# Orbiter_V1.net
KiCad netlist of a schematic drawn in EAGLE
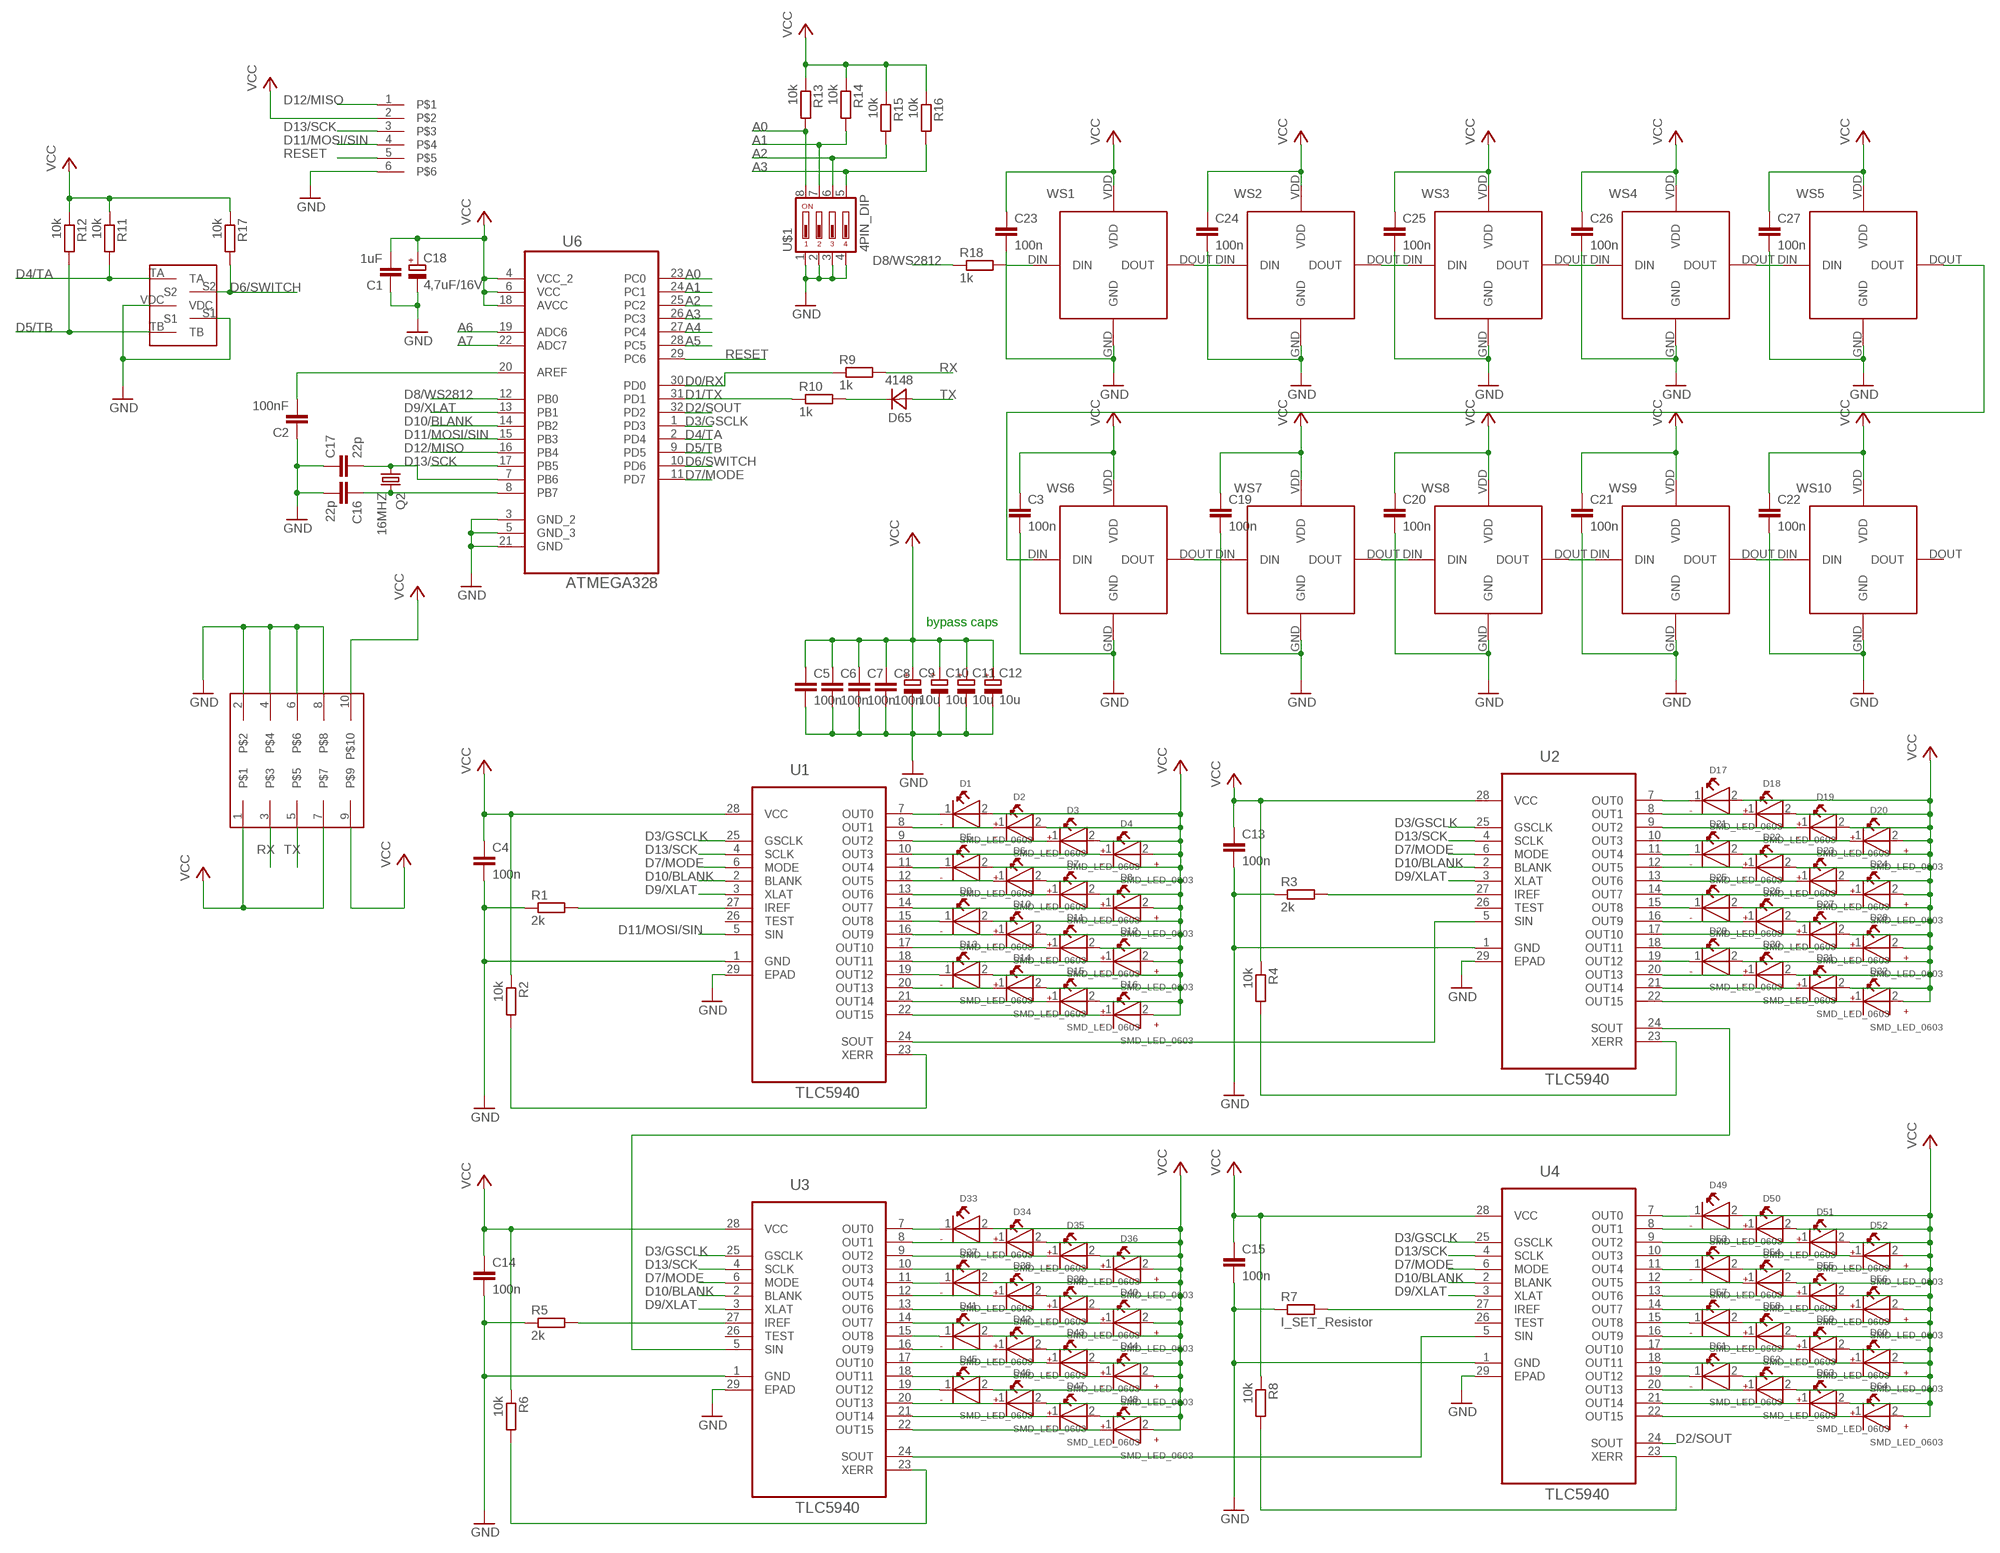
[diagram p0: schematic, sheet 1]

(export (version "E")
  (design (tool "Eeschema 10.0.6"))
  (components
    (comp (ref "C1")
      (value "1uF")
      (footprint "eagle-import:C0603")
      (libsource (lib "eagle-import") (part "KONDENSATOR_0603"))
    )
    (comp (ref "C2")
      (value "100nF")
      (footprint "eagle-import:C0603")
      (libsource (lib "eagle-import") (part "KONDENSATOR_0603"))
    )
    (comp (ref "C3")
      (value "100n")
      (footprint "eagle-import:C0603")
      (libsource (lib "eagle-import") (part "KONDENSATOR_0603"))
    )
    (comp (ref "C4")
      (value "100n")
      (footprint "eagle-import:C0603")
      (libsource (lib "eagle-import") (part "KONDENSATOR_0603"))
    )
    (comp (ref "C5")
      (value "100n")
      (footprint "eagle-import:C0603")
      (libsource (lib "eagle-import") (part "KONDENSATOR_0603"))
    )
    (comp (ref "C6")
      (value "100n")
      (footprint "eagle-import:C0603")
      (libsource (lib "eagle-import") (part "KONDENSATOR_0603"))
    )
    (comp (ref "C7")
      (value "100n")
      (footprint "eagle-import:C0603")
      (libsource (lib "eagle-import") (part "KONDENSATOR_0603"))
    )
    (comp (ref "C8")
      (value "100n")
      (footprint "eagle-import:C0603")
      (libsource (lib "eagle-import") (part "KONDENSATOR_0603"))
    )
    (comp (ref "C9")
      (value "10u")
      (footprint "eagle-import:153CLV-0605")
      (libsource (lib "eagle-import") (part "SMD_ELCTROLYTIC"))
    )
    (comp (ref "C10")
      (value "10u")
      (footprint "eagle-import:153CLV-0605")
      (libsource (lib "eagle-import") (part "SMD_ELCTROLYTIC"))
    )
    (comp (ref "C11")
      (value "10u")
      (footprint "eagle-import:153CLV-0605")
      (libsource (lib "eagle-import") (part "SMD_ELCTROLYTIC"))
    )
    (comp (ref "C12")
      (value "10u")
      (footprint "eagle-import:153CLV-0605")
      (libsource (lib "eagle-import") (part "SMD_ELCTROLYTIC"))
    )
    (comp (ref "C13")
      (value "100n")
      (footprint "eagle-import:C0603")
      (libsource (lib "eagle-import") (part "KONDENSATOR_0603"))
    )
    (comp (ref "C14")
      (value "100n")
      (footprint "eagle-import:C0603")
      (libsource (lib "eagle-import") (part "KONDENSATOR_0603"))
    )
    (comp (ref "C15")
      (value "100n")
      (footprint "eagle-import:C0603")
      (libsource (lib "eagle-import") (part "KONDENSATOR_0603"))
    )
    (comp (ref "C16")
      (value "22p")
      (footprint "eagle-import:C0603")
      (libsource (lib "eagle-import") (part "KONDENSATOR_0603"))
    )
    (comp (ref "C17")
      (value "22p")
      (footprint "eagle-import:C0603")
      (libsource (lib "eagle-import") (part "KONDENSATOR_0603"))
    )
    (comp (ref "C18")
      (value "4,7uF/16V")
      (footprint "eagle-import:153CLV-0605")
      (libsource (lib "eagle-import") (part "SMD_ELCTROLYTIC"))
    )
    (comp (ref "C19")
      (value "100n")
      (footprint "eagle-import:C0603")
      (libsource (lib "eagle-import") (part "KONDENSATOR_0603"))
    )
    (comp (ref "C20")
      (value "100n")
      (footprint "eagle-import:C0603")
      (libsource (lib "eagle-import") (part "KONDENSATOR_0603"))
    )
    (comp (ref "C21")
      (value "100n")
      (footprint "eagle-import:C0603")
      (libsource (lib "eagle-import") (part "KONDENSATOR_0603"))
    )
    (comp (ref "C22")
      (value "100n")
      (footprint "eagle-import:C0603")
      (libsource (lib "eagle-import") (part "KONDENSATOR_0603"))
    )
    (comp (ref "C23")
      (value "100n")
      (footprint "eagle-import:C0603")
      (libsource (lib "eagle-import") (part "KONDENSATOR_0603"))
    )
    (comp (ref "C24")
      (value "100n")
      (footprint "eagle-import:C0603")
      (libsource (lib "eagle-import") (part "KONDENSATOR_0603"))
    )
    (comp (ref "C25")
      (value "100n")
      (footprint "eagle-import:C0603")
      (libsource (lib "eagle-import") (part "KONDENSATOR_0603"))
    )
    (comp (ref "C26")
      (value "100n")
      (footprint "eagle-import:C0603")
      (libsource (lib "eagle-import") (part "KONDENSATOR_0603"))
    )
    (comp (ref "C27")
      (value "100n")
      (footprint "eagle-import:C0603")
      (libsource (lib "eagle-import") (part "KONDENSATOR_0603"))
    )
    (comp (ref "D1")
      (value "SMD_LED_0603")
      (footprint "eagle-import:WL-SMCW_0603")
      (libsource (lib "eagle-import") (part "SMD_LED_0603"))
    )
    (comp (ref "D2")
      (value "SMD_LED_0603")
      (footprint "eagle-import:WL-SMCW_0603")
      (libsource (lib "eagle-import") (part "SMD_LED_0603"))
    )
    (comp (ref "D3")
      (value "SMD_LED_0603")
      (footprint "eagle-import:WL-SMCW_0603")
      (libsource (lib "eagle-import") (part "SMD_LED_0603"))
    )
    (comp (ref "D4")
      (value "SMD_LED_0603")
      (footprint "eagle-import:WL-SMCW_0603")
      (libsource (lib "eagle-import") (part "SMD_LED_0603"))
    )
    (comp (ref "D5")
      (value "SMD_LED_0603")
      (footprint "eagle-import:WL-SMCW_0603")
      (libsource (lib "eagle-import") (part "SMD_LED_0603"))
    )
    (comp (ref "D6")
      (value "SMD_LED_0603")
      (footprint "eagle-import:WL-SMCW_0603")
      (libsource (lib "eagle-import") (part "SMD_LED_0603"))
    )
    (comp (ref "D7")
      (value "SMD_LED_0603")
      (footprint "eagle-import:WL-SMCW_0603")
      (libsource (lib "eagle-import") (part "SMD_LED_0603"))
    )
    (comp (ref "D8")
      (value "SMD_LED_0603")
      (footprint "eagle-import:WL-SMCW_0603")
      (libsource (lib "eagle-import") (part "SMD_LED_0603"))
    )
    (comp (ref "D9")
      (value "SMD_LED_0603")
      (footprint "eagle-import:WL-SMCW_0603")
      (libsource (lib "eagle-import") (part "SMD_LED_0603"))
    )
    (comp (ref "D10")
      (value "SMD_LED_0603")
      (footprint "eagle-import:WL-SMCW_0603")
      (libsource (lib "eagle-import") (part "SMD_LED_0603"))
    )
    (comp (ref "D11")
      (value "SMD_LED_0603")
      (footprint "eagle-import:WL-SMCW_0603")
      (libsource (lib "eagle-import") (part "SMD_LED_0603"))
    )
    (comp (ref "D12")
      (value "SMD_LED_0603")
      (footprint "eagle-import:WL-SMCW_0603")
      (libsource (lib "eagle-import") (part "SMD_LED_0603"))
    )
    (comp (ref "D13")
      (value "SMD_LED_0603")
      (footprint "eagle-import:WL-SMCW_0603")
      (libsource (lib "eagle-import") (part "SMD_LED_0603"))
    )
    (comp (ref "D14")
      (value "SMD_LED_0603")
      (footprint "eagle-import:WL-SMCW_0603")
      (libsource (lib "eagle-import") (part "SMD_LED_0603"))
    )
    (comp (ref "D15")
      (value "SMD_LED_0603")
      (footprint "eagle-import:WL-SMCW_0603")
      (libsource (lib "eagle-import") (part "SMD_LED_0603"))
    )
    (comp (ref "D16")
      (value "SMD_LED_0603")
      (footprint "eagle-import:WL-SMCW_0603")
      (libsource (lib "eagle-import") (part "SMD_LED_0603"))
    )
    (comp (ref "D17")
      (value "SMD_LED_0603")
      (footprint "eagle-import:WL-SMCW_0603")
      (libsource (lib "eagle-import") (part "SMD_LED_0603"))
    )
    (comp (ref "D18")
      (value "SMD_LED_0603")
      (footprint "eagle-import:WL-SMCW_0603")
      (libsource (lib "eagle-import") (part "SMD_LED_0603"))
    )
    (comp (ref "D19")
      (value "SMD_LED_0603")
      (footprint "eagle-import:WL-SMCW_0603")
      (libsource (lib "eagle-import") (part "SMD_LED_0603"))
    )
    (comp (ref "D20")
      (value "SMD_LED_0603")
      (footprint "eagle-import:WL-SMCW_0603")
      (libsource (lib "eagle-import") (part "SMD_LED_0603"))
    )
    (comp (ref "D21")
      (value "SMD_LED_0603")
      (footprint "eagle-import:WL-SMCW_0603")
      (libsource (lib "eagle-import") (part "SMD_LED_0603"))
    )
    (comp (ref "D22")
      (value "SMD_LED_0603")
      (footprint "eagle-import:WL-SMCW_0603")
      (libsource (lib "eagle-import") (part "SMD_LED_0603"))
    )
    (comp (ref "D23")
      (value "SMD_LED_0603")
      (footprint "eagle-import:WL-SMCW_0603")
      (libsource (lib "eagle-import") (part "SMD_LED_0603"))
    )
    (comp (ref "D24")
      (value "SMD_LED_0603")
      (footprint "eagle-import:WL-SMCW_0603")
      (libsource (lib "eagle-import") (part "SMD_LED_0603"))
    )
    (comp (ref "D25")
      (value "SMD_LED_0603")
      (footprint "eagle-import:WL-SMCW_0603")
      (libsource (lib "eagle-import") (part "SMD_LED_0603"))
    )
    (comp (ref "D26")
      (value "SMD_LED_0603")
      (footprint "eagle-import:WL-SMCW_0603")
      (libsource (lib "eagle-import") (part "SMD_LED_0603"))
    )
    (comp (ref "D27")
      (value "SMD_LED_0603")
      (footprint "eagle-import:WL-SMCW_0603")
      (libsource (lib "eagle-import") (part "SMD_LED_0603"))
    )
    (comp (ref "D28")
      (value "SMD_LED_0603")
      (footprint "eagle-import:WL-SMCW_0603")
      (libsource (lib "eagle-import") (part "SMD_LED_0603"))
    )
    (comp (ref "D29")
      (value "SMD_LED_0603")
      (footprint "eagle-import:WL-SMCW_0603")
      (libsource (lib "eagle-import") (part "SMD_LED_0603"))
    )
    (comp (ref "D30")
      (value "SMD_LED_0603")
      (footprint "eagle-import:WL-SMCW_0603")
      (libsource (lib "eagle-import") (part "SMD_LED_0603"))
    )
    (comp (ref "D31")
      (value "SMD_LED_0603")
      (footprint "eagle-import:WL-SMCW_0603")
      (libsource (lib "eagle-import") (part "SMD_LED_0603"))
    )
    (comp (ref "D32")
      (value "SMD_LED_0603")
      (footprint "eagle-import:WL-SMCW_0603")
      (libsource (lib "eagle-import") (part "SMD_LED_0603"))
    )
    (comp (ref "D33")
      (value "SMD_LED_0603")
      (footprint "eagle-import:WL-SMCW_0603")
      (libsource (lib "eagle-import") (part "SMD_LED_0603"))
    )
    (comp (ref "D34")
      (value "SMD_LED_0603")
      (footprint "eagle-import:WL-SMCW_0603")
      (libsource (lib "eagle-import") (part "SMD_LED_0603"))
    )
    (comp (ref "D35")
      (value "SMD_LED_0603")
      (footprint "eagle-import:WL-SMCW_0603")
      (libsource (lib "eagle-import") (part "SMD_LED_0603"))
    )
    (comp (ref "D36")
      (value "SMD_LED_0603")
      (footprint "eagle-import:WL-SMCW_0603")
      (libsource (lib "eagle-import") (part "SMD_LED_0603"))
    )
    (comp (ref "D37")
      (value "SMD_LED_0603")
      (footprint "eagle-import:WL-SMCW_0603")
      (libsource (lib "eagle-import") (part "SMD_LED_0603"))
    )
    (comp (ref "D38")
      (value "SMD_LED_0603")
      (footprint "eagle-import:WL-SMCW_0603")
      (libsource (lib "eagle-import") (part "SMD_LED_0603"))
    )
    (comp (ref "D39")
      (value "SMD_LED_0603")
      (footprint "eagle-import:WL-SMCW_0603")
      (libsource (lib "eagle-import") (part "SMD_LED_0603"))
    )
    (comp (ref "D40")
      (value "SMD_LED_0603")
      (footprint "eagle-import:WL-SMCW_0603")
      (libsource (lib "eagle-import") (part "SMD_LED_0603"))
    )
    (comp (ref "D41")
      (value "SMD_LED_0603")
      (footprint "eagle-import:WL-SMCW_0603")
      (libsource (lib "eagle-import") (part "SMD_LED_0603"))
    )
    (comp (ref "D42")
      (value "SMD_LED_0603")
      (footprint "eagle-import:WL-SMCW_0603")
      (libsource (lib "eagle-import") (part "SMD_LED_0603"))
    )
    (comp (ref "D43")
      (value "SMD_LED_0603")
      (footprint "eagle-import:WL-SMCW_0603")
      (libsource (lib "eagle-import") (part "SMD_LED_0603"))
    )
    (comp (ref "D44")
      (value "SMD_LED_0603")
      (footprint "eagle-import:WL-SMCW_0603")
      (libsource (lib "eagle-import") (part "SMD_LED_0603"))
    )
    (comp (ref "D45")
      (value "SMD_LED_0603")
      (footprint "eagle-import:WL-SMCW_0603")
      (libsource (lib "eagle-import") (part "SMD_LED_0603"))
    )
    (comp (ref "D46")
      (value "SMD_LED_0603")
      (footprint "eagle-import:WL-SMCW_0603")
      (libsource (lib "eagle-import") (part "SMD_LED_0603"))
    )
    (comp (ref "D47")
      (value "SMD_LED_0603")
      (footprint "eagle-import:WL-SMCW_0603")
      (libsource (lib "eagle-import") (part "SMD_LED_0603"))
    )
    (comp (ref "D48")
      (value "SMD_LED_0603")
      (footprint "eagle-import:WL-SMCW_0603")
      (libsource (lib "eagle-import") (part "SMD_LED_0603"))
    )
    (comp (ref "D49")
      (value "SMD_LED_0603")
      (footprint "eagle-import:WL-SMCW_0603")
      (libsource (lib "eagle-import") (part "SMD_LED_0603"))
    )
    (comp (ref "D50")
      (value "SMD_LED_0603")
      (footprint "eagle-import:WL-SMCW_0603")
      (libsource (lib "eagle-import") (part "SMD_LED_0603"))
    )
    (comp (ref "D51")
      (value "SMD_LED_0603")
      (footprint "eagle-import:WL-SMCW_0603")
      (libsource (lib "eagle-import") (part "SMD_LED_0603"))
    )
    (comp (ref "D52")
      (value "SMD_LED_0603")
      (footprint "eagle-import:WL-SMCW_0603")
      (libsource (lib "eagle-import") (part "SMD_LED_0603"))
    )
    (comp (ref "D53")
      (value "SMD_LED_0603")
      (footprint "eagle-import:WL-SMCW_0603")
      (libsource (lib "eagle-import") (part "SMD_LED_0603"))
    )
    (comp (ref "D54")
      (value "SMD_LED_0603")
      (footprint "eagle-import:WL-SMCW_0603")
      (libsource (lib "eagle-import") (part "SMD_LED_0603"))
    )
    (comp (ref "D55")
      (value "SMD_LED_0603")
      (footprint "eagle-import:WL-SMCW_0603")
      (libsource (lib "eagle-import") (part "SMD_LED_0603"))
    )
    (comp (ref "D56")
      (value "SMD_LED_0603")
      (footprint "eagle-import:WL-SMCW_0603")
      (libsource (lib "eagle-import") (part "SMD_LED_0603"))
    )
    (comp (ref "D57")
      (value "SMD_LED_0603")
      (footprint "eagle-import:WL-SMCW_0603")
      (libsource (lib "eagle-import") (part "SMD_LED_0603"))
    )
    (comp (ref "D58")
      (value "SMD_LED_0603")
      (footprint "eagle-import:WL-SMCW_0603")
      (libsource (lib "eagle-import") (part "SMD_LED_0603"))
    )
    (comp (ref "D59")
      (value "SMD_LED_0603")
      (footprint "eagle-import:WL-SMCW_0603")
      (libsource (lib "eagle-import") (part "SMD_LED_0603"))
    )
    (comp (ref "D60")
      (value "SMD_LED_0603")
      (footprint "eagle-import:WL-SMCW_0603")
      (libsource (lib "eagle-import") (part "SMD_LED_0603"))
    )
    (comp (ref "D61")
      (value "SMD_LED_0603")
      (footprint "eagle-import:WL-SMCW_0603")
      (libsource (lib "eagle-import") (part "SMD_LED_0603"))
    )
    (comp (ref "D62")
      (value "SMD_LED_0603")
      (footprint "eagle-import:WL-SMCW_0603")
      (libsource (lib "eagle-import") (part "SMD_LED_0603"))
    )
    (comp (ref "D63")
      (value "SMD_LED_0603")
      (footprint "eagle-import:WL-SMCW_0603")
      (libsource (lib "eagle-import") (part "SMD_LED_0603"))
    )
    (comp (ref "D64")
      (value "SMD_LED_0603")
      (footprint "eagle-import:WL-SMCW_0603")
      (libsource (lib "eagle-import") (part "SMD_LED_0603"))
    )
    (comp (ref "D65")
      (value "4148")
      (footprint "eagle-import:SOD323-R")
      (libsource (lib "eagle-import") (part "4148_SOD323"))
    )
    (comp (ref "Q2")
      (value "16MHZ")
      (footprint "eagle-import:SM49")
      (libsource (lib "eagle-import") (part "CRYSTAL_SM49"))
    )
    (comp (ref "R1")
      (value "2k")
      (footprint "eagle-import:R0805")
      (libsource (lib "eagle-import") (part "WIDERSTAND_0805R0805"))
    )
    (comp (ref "R2")
      (value "10k")
      (footprint "eagle-import:R0805")
      (libsource (lib "eagle-import") (part "WIDERSTAND_0805R0805"))
    )
    (comp (ref "R3")
      (value "2k")
      (footprint "eagle-import:R0805")
      (libsource (lib "eagle-import") (part "WIDERSTAND_0805R0805"))
    )
    (comp (ref "R4")
      (value "10k")
      (footprint "eagle-import:R0805")
      (libsource (lib "eagle-import") (part "WIDERSTAND_0805R0805"))
    )
    (comp (ref "R5")
      (value "2k")
      (footprint "eagle-import:R0805")
      (libsource (lib "eagle-import") (part "WIDERSTAND_0805R0805"))
    )
    (comp (ref "R6")
      (value "10k")
      (footprint "eagle-import:R0805")
      (libsource (lib "eagle-import") (part "WIDERSTAND_0805R0805"))
    )
    (comp (ref "R7")
      (value "I_SET_Resistor")
      (footprint "eagle-import:R0805")
      (libsource (lib "eagle-import") (part "WIDERSTAND_0805R0805"))
    )
    (comp (ref "R8")
      (value "10k")
      (footprint "eagle-import:R0805")
      (libsource (lib "eagle-import") (part "WIDERSTAND_0805R0805"))
    )
    (comp (ref "R9")
      (value "1k")
      (footprint "eagle-import:R0805")
      (libsource (lib "eagle-import") (part "WIDERSTAND_0805R0805"))
    )
    (comp (ref "R10")
      (value "1k")
      (footprint "eagle-import:R0805")
      (libsource (lib "eagle-import") (part "WIDERSTAND_0805R0805"))
    )
    (comp (ref "R11")
      (value "10k")
      (footprint "eagle-import:R0805")
      (libsource (lib "eagle-import") (part "WIDERSTAND_0805R0805"))
    )
    (comp (ref "R12")
      (value "10k")
      (footprint "eagle-import:R0805")
      (libsource (lib "eagle-import") (part "WIDERSTAND_0805R0805"))
    )
    (comp (ref "R13")
      (value "10k")
      (footprint "eagle-import:R0805")
      (libsource (lib "eagle-import") (part "WIDERSTAND_0805R0805"))
    )
    (comp (ref "R14")
      (value "10k")
      (footprint "eagle-import:R0805")
      (libsource (lib "eagle-import") (part "WIDERSTAND_0805R0805"))
    )
    (comp (ref "R15")
      (value "10k")
      (footprint "eagle-import:R0805")
      (libsource (lib "eagle-import") (part "WIDERSTAND_0805R0805"))
    )
    (comp (ref "R16")
      (value "10k")
      (footprint "eagle-import:R0805")
      (libsource (lib "eagle-import") (part "WIDERSTAND_0805R0805"))
    )
    (comp (ref "R17")
      (value "10k")
      (footprint "eagle-import:R0805")
      (libsource (lib "eagle-import") (part "WIDERSTAND_0805R0805"))
    )
    (comp (ref "R18")
      (value "1k")
      (footprint "eagle-import:R0805")
      (libsource (lib "eagle-import") (part "WIDERSTAND_0805R0805"))
    )
    (comp (ref "U$1")
      (value "4PIN_DIP")
      (footprint "eagle-import:CTS-219-04")
      (libsource (lib "eagle-import") (part "4PIN_DIP"))
    )
    (comp (ref "U$2")
      (value "10PIN_HEADER_SMD")
      (footprint "eagle-import:87832-10")
      (libsource (lib "eagle-import") (part "10PIN_HEADER_SMD"))
    )
    (comp (ref "U$3")
      (value "6PIN_HEADER_SMD_OPEN")
      (footprint "eagle-import:6PIN_HEADER_SMD_OPEN")
      (libsource (lib "eagle-import") (part "6PIN_HEADER_SMD_OPEN"))
    )
    (comp (ref "U$4")
      (value "BOURNS_ENCODER")
      (footprint "eagle-import:BOURNS_ENCODER_SMD")
      (libsource (lib "eagle-import") (part "BOURNS_ENCODER"))
    )
    (comp (ref "U1")
      (value "TLC5940")
      (footprint "eagle-import:SOP65P640X120-29N")
      (fields (field (name "MPN") "TLC59401PWP"))
      (libsource (lib "eagle-import") (part "TLC59401PWP"))
    )
    (comp (ref "U2")
      (value "TLC5940")
      (footprint "eagle-import:SOP65P640X120-29N")
      (fields (field (name "MPN") "TLC59401PWP"))
      (libsource (lib "eagle-import") (part "TLC59401PWP"))
    )
    (comp (ref "U3")
      (value "TLC5940")
      (footprint "eagle-import:SOP65P640X120-29N")
      (fields (field (name "MPN") "TLC59401PWP"))
      (libsource (lib "eagle-import") (part "TLC59401PWP"))
    )
    (comp (ref "U4")
      (value "TLC5940")
      (footprint "eagle-import:SOP65P640X120-29N")
      (fields (field (name "MPN") "TLC59401PWP"))
      (libsource (lib "eagle-import") (part "TLC59401PWP"))
    )
    (comp (ref "U6")
      (value "ATMEGA328")
      (footprint "eagle-import:QFP80P900X900X120-32N")
      (fields (field (name "MPN") "ATMEGA328P-AU"))
      (libsource (lib "eagle-import") (part "ATMEGA328P-AU"))
    )
    (comp (ref "WS1")
      (value "WS2812")
      (footprint "eagle-import:WS2812")
      (libsource (lib "eagle-import") (part "WS2812"))
    )
    (comp (ref "WS2")
      (value "WS2812")
      (footprint "eagle-import:WS2812")
      (libsource (lib "eagle-import") (part "WS2812"))
    )
    (comp (ref "WS3")
      (value "WS2812")
      (footprint "eagle-import:WS2812")
      (libsource (lib "eagle-import") (part "WS2812"))
    )
    (comp (ref "WS4")
      (value "WS2812")
      (footprint "eagle-import:WS2812")
      (libsource (lib "eagle-import") (part "WS2812"))
    )
    (comp (ref "WS5")
      (value "WS2812")
      (footprint "eagle-import:WS2812")
      (libsource (lib "eagle-import") (part "WS2812"))
    )
    (comp (ref "WS6")
      (value "WS2812")
      (footprint "eagle-import:WS2812")
      (libsource (lib "eagle-import") (part "WS2812"))
    )
    (comp (ref "WS7")
      (value "WS2812")
      (footprint "eagle-import:WS2812")
      (libsource (lib "eagle-import") (part "WS2812"))
    )
    (comp (ref "WS8")
      (value "WS2812")
      (footprint "eagle-import:WS2812")
      (libsource (lib "eagle-import") (part "WS2812"))
    )
    (comp (ref "WS9")
      (value "WS2812")
      (footprint "eagle-import:WS2812")
      (libsource (lib "eagle-import") (part "WS2812"))
    )
    (comp (ref "WS10")
      (value "WS2812")
      (footprint "eagle-import:WS2812")
      (libsource (lib "eagle-import") (part "WS2812"))
    )
  )
  (nets
    (net (code "1") (name "/A0") (class "Default")
      (node (ref "R13") (pin "2") (pinfunction "2_2") (pintype "passive"))
      (node (ref "U$1") (pin "8") (pinfunction "8_8") (pintype "passive"))
      (node (ref "U6") (pin "23") (pinfunction "PC0_23") (pintype "bidirectional"))
    )
    (net (code "2") (name "/A1") (class "Default")
      (node (ref "R14") (pin "2") (pinfunction "2_2") (pintype "passive"))
      (node (ref "U$1") (pin "7") (pinfunction "7_7") (pintype "passive"))
      (node (ref "U6") (pin "24") (pinfunction "PC1_24") (pintype "bidirectional"))
    )
    (net (code "3") (name "/A2") (class "Default")
      (node (ref "R15") (pin "2") (pinfunction "2_2") (pintype "passive"))
      (node (ref "U$1") (pin "6") (pinfunction "6_6") (pintype "passive"))
      (node (ref "U6") (pin "25") (pinfunction "PC2_25") (pintype "bidirectional"))
    )
    (net (code "4") (name "/A3") (class "Default")
      (node (ref "R16") (pin "2") (pinfunction "2_2") (pintype "passive"))
      (node (ref "U$1") (pin "5") (pinfunction "5_5") (pintype "passive"))
      (node (ref "U6") (pin "26") (pinfunction "PC3_26") (pintype "bidirectional"))
    )
    (net (code "5") (name "/A4") (class "Default")
      (node (ref "U6") (pin "27") (pinfunction "PC4_27") (pintype "bidirectional"))
    )
    (net (code "6") (name "/A5") (class "Default")
      (node (ref "U6") (pin "28") (pinfunction "PC5_28") (pintype "bidirectional"))
    )
    (net (code "7") (name "/A6") (class "Default")
      (node (ref "U6") (pin "19") (pinfunction "ADC6_19") (pintype "input"))
    )
    (net (code "8") (name "/A7") (class "Default")
      (node (ref "U6") (pin "22") (pinfunction "ADC7_22") (pintype "input"))
    )
    (net (code "9") (name "/D0{slash}RX") (class "Default")
      (node (ref "R9") (pin "1") (pinfunction "1_1") (pintype "passive"))
      (node (ref "U6") (pin "30") (pinfunction "PD0_30") (pintype "bidirectional"))
    )
    (net (code "10") (name "/D1{slash}TX") (class "Default")
      (node (ref "R10") (pin "1") (pinfunction "1_1") (pintype "passive"))
      (node (ref "U6") (pin "31") (pinfunction "PD1_31") (pintype "bidirectional"))
    )
    (net (code "11") (name "/D2{slash}SOUT") (class "Default")
      (node (ref "U4") (pin "24") (pinfunction "SOUT_24") (pintype "output"))
      (node (ref "U6") (pin "32") (pinfunction "PD2_32") (pintype "bidirectional"))
    )
    (net (code "12") (name "/D3{slash}GSCLK") (class "Default")
      (node (ref "U1") (pin "25") (pinfunction "GSCLK_25") (pintype "input"))
      (node (ref "U2") (pin "25") (pinfunction "GSCLK_25") (pintype "input"))
      (node (ref "U3") (pin "25") (pinfunction "GSCLK_25") (pintype "input"))
      (node (ref "U4") (pin "25") (pinfunction "GSCLK_25") (pintype "input"))
      (node (ref "U6") (pin "1") (pinfunction "PD3_1") (pintype "bidirectional"))
    )
    (net (code "13") (name "/D4{slash}TA") (class "Default")
      (node (ref "R11") (pin "2") (pinfunction "2_2") (pintype "passive"))
      (node (ref "U$4") (pin "TA") (pinfunction "TA_TA") (pintype "bidirectional"))
      (node (ref "U6") (pin "2") (pinfunction "PD4_2") (pintype "bidirectional"))
    )
    (net (code "14") (name "/D5{slash}TB") (class "Default")
      (node (ref "R12") (pin "2") (pinfunction "2_2") (pintype "passive"))
      (node (ref "U$4") (pin "TB") (pinfunction "TB_TB") (pintype "bidirectional"))
      (node (ref "U6") (pin "9") (pinfunction "PD5_9") (pintype "bidirectional"))
    )
    (net (code "15") (name "/D6{slash}SWITCH") (class "Default")
      (node (ref "R17") (pin "2") (pinfunction "2_2") (pintype "passive"))
      (node (ref "U$4") (pin "S2") (pinfunction "S2_S2") (pintype "bidirectional"))
      (node (ref "U6") (pin "10") (pinfunction "PD6_10") (pintype "bidirectional"))
    )
    (net (code "16") (name "/D7{slash}MODE") (class "Default")
      (node (ref "U1") (pin "6") (pinfunction "MODE_6") (pintype "input"))
      (node (ref "U2") (pin "6") (pinfunction "MODE_6") (pintype "input"))
      (node (ref "U3") (pin "6") (pinfunction "MODE_6") (pintype "input"))
      (node (ref "U4") (pin "6") (pinfunction "MODE_6") (pintype "input"))
      (node (ref "U6") (pin "11") (pinfunction "PD7_11") (pintype "bidirectional"))
    )
    (net (code "17") (name "/D8{slash}WS2812") (class "Default")
      (node (ref "R18") (pin "1") (pinfunction "1_1") (pintype "passive"))
      (node (ref "U6") (pin "12") (pinfunction "PB0_12") (pintype "bidirectional"))
    )
    (net (code "18") (name "/D9{slash}XLAT") (class "Default")
      (node (ref "U1") (pin "3") (pinfunction "XLAT_3") (pintype "input"))
      (node (ref "U2") (pin "3") (pinfunction "XLAT_3") (pintype "input"))
      (node (ref "U3") (pin "3") (pinfunction "XLAT_3") (pintype "input"))
      (node (ref "U4") (pin "3") (pinfunction "XLAT_3") (pintype "input"))
      (node (ref "U6") (pin "13") (pinfunction "PB1_13") (pintype "bidirectional"))
    )
    (net (code "19") (name "/D10{slash}BLANK") (class "Default")
      (node (ref "U1") (pin "2") (pinfunction "BLANK_2") (pintype "input"))
      (node (ref "U2") (pin "2") (pinfunction "BLANK_2") (pintype "input"))
      (node (ref "U3") (pin "2") (pinfunction "BLANK_2") (pintype "input"))
      (node (ref "U4") (pin "2") (pinfunction "BLANK_2") (pintype "input"))
      (node (ref "U6") (pin "14") (pinfunction "PB2_14") (pintype "bidirectional"))
    )
    (net (code "20") (name "/D11{slash}MOSI{slash}SIN") (class "Default")
      (node (ref "U$3") (pin "4") (pinfunction "P$4_4") (pintype "bidirectional"))
      (node (ref "U1") (pin "5") (pinfunction "SIN_5") (pintype "input"))
      (node (ref "U6") (pin "15") (pinfunction "PB3_15") (pintype "bidirectional"))
    )
    (net (code "21") (name "/D12{slash}MISO") (class "Default")
      (node (ref "U$3") (pin "1") (pinfunction "P$1_1") (pintype "bidirectional"))
      (node (ref "U6") (pin "16") (pinfunction "PB4_16") (pintype "bidirectional"))
    )
    (net (code "22") (name "/D13{slash}SCK") (class "Default")
      (node (ref "U$3") (pin "3") (pinfunction "P$3_3") (pintype "bidirectional"))
      (node (ref "U1") (pin "4") (pinfunction "SCLK_4") (pintype "input"))
      (node (ref "U2") (pin "4") (pinfunction "SCLK_4") (pintype "input"))
      (node (ref "U3") (pin "4") (pinfunction "SCLK_4") (pintype "input"))
      (node (ref "U4") (pin "4") (pinfunction "SCLK_4") (pintype "input"))
      (node (ref "U6") (pin "17") (pinfunction "PB5_17") (pintype "bidirectional"))
    )
    (net (code "23") (name "/RESET") (class "Default")
      (node (ref "U$3") (pin "5") (pinfunction "P$5_5") (pintype "bidirectional"))
      (node (ref "U6") (pin "29") (pinfunction "PC6_29") (pintype "bidirectional"))
    )
    (net (code "24") (name "/RX") (class "Default")
      (node (ref "R9") (pin "2") (pinfunction "2_2") (pintype "passive"))
      (node (ref "U$2") (pin "3") (pinfunction "P$3_3") (pintype "bidirectional"))
    )
    (net (code "25") (name "/TX") (class "Default")
      (node (ref "D65") (pin "A") (pinfunction "A_A") (pintype "passive"))
      (node (ref "U$2") (pin "5") (pinfunction "P$5_5") (pintype "bidirectional"))
    )
    (net (code "26") (name "GND") (class "Default")
      (node (ref "C1") (pin "1") (pinfunction "1_1") (pintype "passive"))
      (node (ref "C10") (pin "-") (pinfunction "-_-") (pintype "passive"))
      (node (ref "C11") (pin "-") (pinfunction "-_-") (pintype "passive"))
      (node (ref "C12") (pin "-") (pinfunction "-_-") (pintype "passive"))
      (node (ref "C13") (pin "2") (pinfunction "2_2") (pintype "passive"))
      (node (ref "C14") (pin "2") (pinfunction "2_2") (pintype "passive"))
      (node (ref "C15") (pin "2") (pinfunction "2_2") (pintype "passive"))
      (node (ref "C16") (pin "2") (pinfunction "2_2") (pintype "passive"))
      (node (ref "C17") (pin "1") (pinfunction "1_1") (pintype "passive"))
      (node (ref "C18") (pin "-") (pinfunction "-_-") (pintype "passive"))
      (node (ref "C19") (pin "2") (pinfunction "2_2") (pintype "passive"))
      (node (ref "C2") (pin "1") (pinfunction "1_1") (pintype "passive"))
      (node (ref "C20") (pin "2") (pinfunction "2_2") (pintype "passive"))
      (node (ref "C21") (pin "2") (pinfunction "2_2") (pintype "passive"))
      (node (ref "C22") (pin "2") (pinfunction "2_2") (pintype "passive"))
      (node (ref "C23") (pin "2") (pinfunction "2_2") (pintype "passive"))
      (node (ref "C24") (pin "2") (pinfunction "2_2") (pintype "passive"))
      (node (ref "C25") (pin "2") (pinfunction "2_2") (pintype "passive"))
      (node (ref "C26") (pin "2") (pinfunction "2_2") (pintype "passive"))
      (node (ref "C27") (pin "2") (pinfunction "2_2") (pintype "passive"))
      (node (ref "C3") (pin "2") (pinfunction "2_2") (pintype "passive"))
      (node (ref "C4") (pin "2") (pinfunction "2_2") (pintype "passive"))
      (node (ref "C5") (pin "2") (pinfunction "2_2") (pintype "passive"))
      (node (ref "C6") (pin "2") (pinfunction "2_2") (pintype "passive"))
      (node (ref "C7") (pin "2") (pinfunction "2_2") (pintype "passive"))
      (node (ref "C8") (pin "2") (pinfunction "2_2") (pintype "passive"))
      (node (ref "C9") (pin "-") (pinfunction "-_-") (pintype "passive"))
      (node (ref "R1") (pin "1") (pinfunction "1_1") (pintype "passive"))
      (node (ref "R3") (pin "1") (pinfunction "1_1") (pintype "passive"))
      (node (ref "R5") (pin "1") (pinfunction "1_1") (pintype "passive"))
      (node (ref "R7") (pin "1") (pinfunction "1_1") (pintype "passive"))
      (node (ref "U$1") (pin "1") (pinfunction "1_1") (pintype "passive"))
      (node (ref "U$1") (pin "2") (pinfunction "2_2") (pintype "passive"))
      (node (ref "U$1") (pin "3") (pinfunction "3_3") (pintype "passive"))
      (node (ref "U$1") (pin "4") (pinfunction "4_4") (pintype "passive"))
      (node (ref "U$2") (pin "2") (pinfunction "P$2_2") (pintype "bidirectional"))
      (node (ref "U$2") (pin "4") (pinfunction "P$4_4") (pintype "bidirectional"))
      (node (ref "U$2") (pin "6") (pinfunction "P$6_6") (pintype "bidirectional"))
      (node (ref "U$2") (pin "8") (pinfunction "P$8_8") (pintype "bidirectional"))
      (node (ref "U$3") (pin "6") (pinfunction "P$6_6") (pintype "bidirectional"))
      (node (ref "U$4") (pin "S1") (pinfunction "S1_S1") (pintype "bidirectional"))
      (node (ref "U$4") (pin "VDC") (pinfunction "VDC_VDC") (pintype "bidirectional"))
      (node (ref "U1") (pin "1") (pinfunction "GND_1") (pintype "passive"))
      (node (ref "U1") (pin "29") (pinfunction "EPAD_29") (pintype "passive"))
      (node (ref "U2") (pin "1") (pinfunction "GND_1") (pintype "passive"))
      (node (ref "U2") (pin "29") (pinfunction "EPAD_29") (pintype "passive"))
      (node (ref "U3") (pin "1") (pinfunction "GND_1") (pintype "passive"))
      (node (ref "U3") (pin "29") (pinfunction "EPAD_29") (pintype "passive"))
      (node (ref "U4") (pin "1") (pinfunction "GND_1") (pintype "passive"))
      (node (ref "U4") (pin "29") (pinfunction "EPAD_29") (pintype "passive"))
      (node (ref "U6") (pin "21") (pinfunction "GND_21") (pintype "passive"))
      (node (ref "U6") (pin "3") (pinfunction "GND_2_3") (pintype "passive"))
      (node (ref "U6") (pin "5") (pinfunction "GND_3_5") (pintype "passive"))
      (node (ref "WS1") (pin "GND") (pinfunction "GND_GND") (pintype "bidirectional"))
      (node (ref "WS10") (pin "GND") (pinfunction "GND_GND") (pintype "bidirectional"))
      (node (ref "WS2") (pin "GND") (pinfunction "GND_GND") (pintype "bidirectional"))
      (node (ref "WS3") (pin "GND") (pinfunction "GND_GND") (pintype "bidirectional"))
      (node (ref "WS4") (pin "GND") (pinfunction "GND_GND") (pintype "bidirectional"))
      (node (ref "WS5") (pin "GND") (pinfunction "GND_GND") (pintype "bidirectional"))
      (node (ref "WS6") (pin "GND") (pinfunction "GND_GND") (pintype "bidirectional"))
      (node (ref "WS7") (pin "GND") (pinfunction "GND_GND") (pintype "bidirectional"))
      (node (ref "WS8") (pin "GND") (pinfunction "GND_GND") (pintype "bidirectional"))
      (node (ref "WS9") (pin "GND") (pinfunction "GND_GND") (pintype "bidirectional"))
    )
    (net (code "27") (name "Net-(D1--)") (class "Default")
      (node (ref "D1") (pin "1") (pinfunction "-_1") (pintype "passive"))
      (node (ref "U1") (pin "7") (pinfunction "OUT0_7") (pintype "output"))
    )
    (net (code "28") (name "Net-(D2--)") (class "Default")
      (node (ref "D2") (pin "1") (pinfunction "-_1") (pintype "passive"))
      (node (ref "U1") (pin "8") (pinfunction "OUT1_8") (pintype "output"))
    )
    (net (code "29") (name "Net-(D3--)") (class "Default")
      (node (ref "D3") (pin "1") (pinfunction "-_1") (pintype "passive"))
      (node (ref "U1") (pin "9") (pinfunction "OUT2_9") (pintype "output"))
    )
    (net (code "30") (name "Net-(D4--)") (class "Default")
      (node (ref "D4") (pin "1") (pinfunction "-_1") (pintype "passive"))
      (node (ref "U1") (pin "10") (pinfunction "OUT3_10") (pintype "output"))
    )
    (net (code "31") (name "Net-(D5--)") (class "Default")
      (node (ref "D5") (pin "1") (pinfunction "-_1") (pintype "passive"))
      (node (ref "U1") (pin "11") (pinfunction "OUT4_11") (pintype "output"))
    )
    (net (code "32") (name "Net-(D6--)") (class "Default")
      (node (ref "D6") (pin "1") (pinfunction "-_1") (pintype "passive"))
      (node (ref "U1") (pin "12") (pinfunction "OUT5_12") (pintype "output"))
    )
    (net (code "33") (name "Net-(D7--)") (class "Default")
      (node (ref "D7") (pin "1") (pinfunction "-_1") (pintype "passive"))
      (node (ref "U1") (pin "13") (pinfunction "OUT6_13") (pintype "output"))
    )
    (net (code "34") (name "Net-(D8--)") (class "Default")
      (node (ref "D8") (pin "1") (pinfunction "-_1") (pintype "passive"))
      (node (ref "U1") (pin "14") (pinfunction "OUT7_14") (pintype "output"))
    )
    (net (code "35") (name "Net-(D9--)") (class "Default")
      (node (ref "D9") (pin "1") (pinfunction "-_1") (pintype "passive"))
      (node (ref "U1") (pin "15") (pinfunction "OUT8_15") (pintype "output"))
    )
    (net (code "36") (name "Net-(D10--)") (class "Default")
      (node (ref "D10") (pin "1") (pinfunction "-_1") (pintype "passive"))
      (node (ref "U1") (pin "16") (pinfunction "OUT9_16") (pintype "output"))
    )
    (net (code "37") (name "Net-(D11--)") (class "Default")
      (node (ref "D11") (pin "1") (pinfunction "-_1") (pintype "passive"))
      (node (ref "U1") (pin "17") (pinfunction "OUT10_17") (pintype "output"))
    )
    (net (code "38") (name "Net-(D12--)") (class "Default")
      (node (ref "D12") (pin "1") (pinfunction "-_1") (pintype "passive"))
      (node (ref "U1") (pin "18") (pinfunction "OUT11_18") (pintype "output"))
    )
    (net (code "39") (name "Net-(D13--)") (class "Default")
      (node (ref "D13") (pin "1") (pinfunction "-_1") (pintype "passive"))
      (node (ref "U1") (pin "19") (pinfunction "OUT12_19") (pintype "output"))
    )
    (net (code "40") (name "Net-(D14--)") (class "Default")
      (node (ref "D14") (pin "1") (pinfunction "-_1") (pintype "passive"))
      (node (ref "U1") (pin "20") (pinfunction "OUT13_20") (pintype "output"))
    )
    (net (code "41") (name "Net-(D15--)") (class "Default")
      (node (ref "D15") (pin "1") (pinfunction "-_1") (pintype "passive"))
      (node (ref "U1") (pin "21") (pinfunction "OUT14_21") (pintype "output"))
    )
    (net (code "42") (name "Net-(D16--)") (class "Default")
      (node (ref "D16") (pin "1") (pinfunction "-_1") (pintype "passive"))
      (node (ref "U1") (pin "22") (pinfunction "OUT15_22") (pintype "output"))
    )
    (net (code "43") (name "Net-(D17--)") (class "Default")
      (node (ref "D17") (pin "1") (pinfunction "-_1") (pintype "passive"))
      (node (ref "U2") (pin "7") (pinfunction "OUT0_7") (pintype "output"))
    )
    (net (code "44") (name "Net-(D18--)") (class "Default")
      (node (ref "D18") (pin "1") (pinfunction "-_1") (pintype "passive"))
      (node (ref "U2") (pin "8") (pinfunction "OUT1_8") (pintype "output"))
    )
    (net (code "45") (name "Net-(D19--)") (class "Default")
      (node (ref "D19") (pin "1") (pinfunction "-_1") (pintype "passive"))
      (node (ref "U2") (pin "9") (pinfunction "OUT2_9") (pintype "output"))
    )
    (net (code "46") (name "Net-(D20--)") (class "Default")
      (node (ref "D20") (pin "1") (pinfunction "-_1") (pintype "passive"))
      (node (ref "U2") (pin "10") (pinfunction "OUT3_10") (pintype "output"))
    )
    (net (code "47") (name "Net-(D21--)") (class "Default")
      (node (ref "D21") (pin "1") (pinfunction "-_1") (pintype "passive"))
      (node (ref "U2") (pin "11") (pinfunction "OUT4_11") (pintype "output"))
    )
    (net (code "48") (name "Net-(D22--)") (class "Default")
      (node (ref "D22") (pin "1") (pinfunction "-_1") (pintype "passive"))
      (node (ref "U2") (pin "12") (pinfunction "OUT5_12") (pintype "output"))
    )
    (net (code "49") (name "Net-(D23--)") (class "Default")
      (node (ref "D23") (pin "1") (pinfunction "-_1") (pintype "passive"))
      (node (ref "U2") (pin "13") (pinfunction "OUT6_13") (pintype "output"))
    )
    (net (code "50") (name "Net-(D24--)") (class "Default")
      (node (ref "D24") (pin "1") (pinfunction "-_1") (pintype "passive"))
      (node (ref "U2") (pin "14") (pinfunction "OUT7_14") (pintype "output"))
    )
    (net (code "51") (name "Net-(D25--)") (class "Default")
      (node (ref "D25") (pin "1") (pinfunction "-_1") (pintype "passive"))
      (node (ref "U2") (pin "15") (pinfunction "OUT8_15") (pintype "output"))
    )
    (net (code "52") (name "Net-(D26--)") (class "Default")
      (node (ref "D26") (pin "1") (pinfunction "-_1") (pintype "passive"))
      (node (ref "U2") (pin "16") (pinfunction "OUT9_16") (pintype "output"))
    )
    (net (code "53") (name "Net-(D27--)") (class "Default")
      (node (ref "D27") (pin "1") (pinfunction "-_1") (pintype "passive"))
      (node (ref "U2") (pin "17") (pinfunction "OUT10_17") (pintype "output"))
    )
    (net (code "54") (name "Net-(D28--)") (class "Default")
      (node (ref "D28") (pin "1") (pinfunction "-_1") (pintype "passive"))
      (node (ref "U2") (pin "18") (pinfunction "OUT11_18") (pintype "output"))
    )
    (net (code "55") (name "Net-(D29--)") (class "Default")
      (node (ref "D29") (pin "1") (pinfunction "-_1") (pintype "passive"))
      (node (ref "U2") (pin "19") (pinfunction "OUT12_19") (pintype "output"))
    )
    (net (code "56") (name "Net-(D30--)") (class "Default")
      (node (ref "D30") (pin "1") (pinfunction "-_1") (pintype "passive"))
      (node (ref "U2") (pin "20") (pinfunction "OUT13_20") (pintype "output"))
    )
    (net (code "57") (name "Net-(D31--)") (class "Default")
      (node (ref "D31") (pin "1") (pinfunction "-_1") (pintype "passive"))
      (node (ref "U2") (pin "21") (pinfunction "OUT14_21") (pintype "output"))
    )
    (net (code "58") (name "Net-(D32--)") (class "Default")
      (node (ref "D32") (pin "1") (pinfunction "-_1") (pintype "passive"))
      (node (ref "U2") (pin "22") (pinfunction "OUT15_22") (pintype "output"))
    )
    (net (code "59") (name "Net-(D33--)") (class "Default")
      (node (ref "D33") (pin "1") (pinfunction "-_1") (pintype "passive"))
      (node (ref "U3") (pin "7") (pinfunction "OUT0_7") (pintype "output"))
    )
    (net (code "60") (name "Net-(D34--)") (class "Default")
      (node (ref "D34") (pin "1") (pinfunction "-_1") (pintype "passive"))
      (node (ref "U3") (pin "8") (pinfunction "OUT1_8") (pintype "output"))
    )
    (net (code "61") (name "Net-(D35--)") (class "Default")
      (node (ref "D35") (pin "1") (pinfunction "-_1") (pintype "passive"))
      (node (ref "U3") (pin "9") (pinfunction "OUT2_9") (pintype "output"))
    )
    (net (code "62") (name "Net-(D36--)") (class "Default")
      (node (ref "D36") (pin "1") (pinfunction "-_1") (pintype "passive"))
      (node (ref "U3") (pin "10") (pinfunction "OUT3_10") (pintype "output"))
    )
    (net (code "63") (name "Net-(D37--)") (class "Default")
      (node (ref "D37") (pin "1") (pinfunction "-_1") (pintype "passive"))
      (node (ref "U3") (pin "11") (pinfunction "OUT4_11") (pintype "output"))
    )
    (net (code "64") (name "Net-(D38--)") (class "Default")
      (node (ref "D38") (pin "1") (pinfunction "-_1") (pintype "passive"))
      (node (ref "U3") (pin "12") (pinfunction "OUT5_12") (pintype "output"))
    )
    (net (code "65") (name "Net-(D39--)") (class "Default")
      (node (ref "D39") (pin "1") (pinfunction "-_1") (pintype "passive"))
      (node (ref "U3") (pin "13") (pinfunction "OUT6_13") (pintype "output"))
    )
    (net (code "66") (name "Net-(D40--)") (class "Default")
      (node (ref "D40") (pin "1") (pinfunction "-_1") (pintype "passive"))
      (node (ref "U3") (pin "14") (pinfunction "OUT7_14") (pintype "output"))
    )
    (net (code "67") (name "Net-(D41--)") (class "Default")
      (node (ref "D41") (pin "1") (pinfunction "-_1") (pintype "passive"))
      (node (ref "U3") (pin "15") (pinfunction "OUT8_15") (pintype "output"))
    )
    (net (code "68") (name "Net-(D42--)") (class "Default")
      (node (ref "D42") (pin "1") (pinfunction "-_1") (pintype "passive"))
      (node (ref "U3") (pin "16") (pinfunction "OUT9_16") (pintype "output"))
    )
    (net (code "69") (name "Net-(D43--)") (class "Default")
      (node (ref "D43") (pin "1") (pinfunction "-_1") (pintype "passive"))
      (node (ref "U3") (pin "17") (pinfunction "OUT10_17") (pintype "output"))
    )
    (net (code "70") (name "Net-(D44--)") (class "Default")
      (node (ref "D44") (pin "1") (pinfunction "-_1") (pintype "passive"))
      (node (ref "U3") (pin "18") (pinfunction "OUT11_18") (pintype "output"))
    )
    (net (code "71") (name "Net-(D45--)") (class "Default")
      (node (ref "D45") (pin "1") (pinfunction "-_1") (pintype "passive"))
      (node (ref "U3") (pin "19") (pinfunction "OUT12_19") (pintype "output"))
    )
    (net (code "72") (name "Net-(D46--)") (class "Default")
      (node (ref "D46") (pin "1") (pinfunction "-_1") (pintype "passive"))
      (node (ref "U3") (pin "20") (pinfunction "OUT13_20") (pintype "output"))
    )
    (net (code "73") (name "Net-(D47--)") (class "Default")
      (node (ref "D47") (pin "1") (pinfunction "-_1") (pintype "passive"))
      (node (ref "U3") (pin "21") (pinfunction "OUT14_21") (pintype "output"))
    )
    (net (code "74") (name "Net-(D48--)") (class "Default")
      (node (ref "D48") (pin "1") (pinfunction "-_1") (pintype "passive"))
      (node (ref "U3") (pin "22") (pinfunction "OUT15_22") (pintype "output"))
    )
    (net (code "75") (name "Net-(D49--)") (class "Default")
      (node (ref "D49") (pin "1") (pinfunction "-_1") (pintype "passive"))
      (node (ref "U4") (pin "7") (pinfunction "OUT0_7") (pintype "output"))
    )
    (net (code "76") (name "Net-(D50--)") (class "Default")
      (node (ref "D50") (pin "1") (pinfunction "-_1") (pintype "passive"))
      (node (ref "U4") (pin "8") (pinfunction "OUT1_8") (pintype "output"))
    )
    (net (code "77") (name "Net-(D51--)") (class "Default")
      (node (ref "D51") (pin "1") (pinfunction "-_1") (pintype "passive"))
      (node (ref "U4") (pin "9") (pinfunction "OUT2_9") (pintype "output"))
    )
    (net (code "78") (name "Net-(D52--)") (class "Default")
      (node (ref "D52") (pin "1") (pinfunction "-_1") (pintype "passive"))
      (node (ref "U4") (pin "10") (pinfunction "OUT3_10") (pintype "output"))
    )
    (net (code "79") (name "Net-(D53--)") (class "Default")
      (node (ref "D53") (pin "1") (pinfunction "-_1") (pintype "passive"))
      (node (ref "U4") (pin "11") (pinfunction "OUT4_11") (pintype "output"))
    )
    (net (code "80") (name "Net-(D54--)") (class "Default")
      (node (ref "D54") (pin "1") (pinfunction "-_1") (pintype "passive"))
      (node (ref "U4") (pin "12") (pinfunction "OUT5_12") (pintype "output"))
    )
    (net (code "81") (name "Net-(D55--)") (class "Default")
      (node (ref "D55") (pin "1") (pinfunction "-_1") (pintype "passive"))
      (node (ref "U4") (pin "13") (pinfunction "OUT6_13") (pintype "output"))
    )
    (net (code "82") (name "Net-(D56--)") (class "Default")
      (node (ref "D56") (pin "1") (pinfunction "-_1") (pintype "passive"))
      (node (ref "U4") (pin "14") (pinfunction "OUT7_14") (pintype "output"))
    )
    (net (code "83") (name "Net-(D57--)") (class "Default")
      (node (ref "D57") (pin "1") (pinfunction "-_1") (pintype "passive"))
      (node (ref "U4") (pin "15") (pinfunction "OUT8_15") (pintype "output"))
    )
    (net (code "84") (name "Net-(D58--)") (class "Default")
      (node (ref "D58") (pin "1") (pinfunction "-_1") (pintype "passive"))
      (node (ref "U4") (pin "16") (pinfunction "OUT9_16") (pintype "output"))
    )
    (net (code "85") (name "Net-(D59--)") (class "Default")
      (node (ref "D59") (pin "1") (pinfunction "-_1") (pintype "passive"))
      (node (ref "U4") (pin "17") (pinfunction "OUT10_17") (pintype "output"))
    )
    (net (code "86") (name "Net-(D60--)") (class "Default")
      (node (ref "D60") (pin "1") (pinfunction "-_1") (pintype "passive"))
      (node (ref "U4") (pin "18") (pinfunction "OUT11_18") (pintype "output"))
    )
    (net (code "87") (name "Net-(D61--)") (class "Default")
      (node (ref "D61") (pin "1") (pinfunction "-_1") (pintype "passive"))
      (node (ref "U4") (pin "19") (pinfunction "OUT12_19") (pintype "output"))
    )
    (net (code "88") (name "Net-(D62--)") (class "Default")
      (node (ref "D62") (pin "1") (pinfunction "-_1") (pintype "passive"))
      (node (ref "U4") (pin "20") (pinfunction "OUT13_20") (pintype "output"))
    )
    (net (code "89") (name "Net-(D63--)") (class "Default")
      (node (ref "D63") (pin "1") (pinfunction "-_1") (pintype "passive"))
      (node (ref "U4") (pin "21") (pinfunction "OUT14_21") (pintype "output"))
    )
    (net (code "90") (name "Net-(D64--)") (class "Default")
      (node (ref "D64") (pin "1") (pinfunction "-_1") (pintype "passive"))
      (node (ref "U4") (pin "22") (pinfunction "OUT15_22") (pintype "output"))
    )
    (net (code "91") (name "Net-(D65-PadC)") (class "Default")
      (node (ref "D65") (pin "C") (pinfunction "C_C") (pintype "passive"))
      (node (ref "R10") (pin "2") (pinfunction "2_2") (pintype "passive"))
    )
    (net (code "92") (name "Net-(R18-Pad2)") (class "Default")
      (node (ref "R18") (pin "2") (pinfunction "2_2") (pintype "passive"))
      (node (ref "WS1") (pin "DIN") (pinfunction "DIN_DIN") (pintype "bidirectional"))
    )
    (net (code "93") (name "Net-(U1-IREF)") (class "Default")
      (node (ref "R1") (pin "2") (pinfunction "2_2") (pintype "passive"))
      (node (ref "U1") (pin "27") (pinfunction "IREF_27") (pintype "input"))
    )
    (net (code "94") (name "Net-(U1-SOUT)") (class "Default")
      (node (ref "U1") (pin "24") (pinfunction "SOUT_24") (pintype "output"))
      (node (ref "U2") (pin "5") (pinfunction "SIN_5") (pintype "input"))
    )
    (net (code "95") (name "Net-(U1-XERR)") (class "Default")
      (node (ref "R2") (pin "2") (pinfunction "2_2") (pintype "passive"))
      (node (ref "U1") (pin "23") (pinfunction "XERR_23") (pintype "output"))
    )
    (net (code "96") (name "Net-(U2-IREF)") (class "Default")
      (node (ref "R3") (pin "2") (pinfunction "2_2") (pintype "passive"))
      (node (ref "U2") (pin "27") (pinfunction "IREF_27") (pintype "input"))
    )
    (net (code "97") (name "Net-(U2-SOUT)") (class "Default")
      (node (ref "U2") (pin "24") (pinfunction "SOUT_24") (pintype "output"))
      (node (ref "U3") (pin "5") (pinfunction "SIN_5") (pintype "input"))
    )
    (net (code "98") (name "Net-(U2-XERR)") (class "Default")
      (node (ref "R4") (pin "2") (pinfunction "2_2") (pintype "passive"))
      (node (ref "U2") (pin "23") (pinfunction "XERR_23") (pintype "output"))
    )
    (net (code "99") (name "Net-(U3-IREF)") (class "Default")
      (node (ref "R5") (pin "2") (pinfunction "2_2") (pintype "passive"))
      (node (ref "U3") (pin "27") (pinfunction "IREF_27") (pintype "input"))
    )
    (net (code "100") (name "Net-(U3-SOUT)") (class "Default")
      (node (ref "U3") (pin "24") (pinfunction "SOUT_24") (pintype "output"))
      (node (ref "U4") (pin "5") (pinfunction "SIN_5") (pintype "input"))
    )
    (net (code "101") (name "Net-(U3-XERR)") (class "Default")
      (node (ref "R6") (pin "2") (pinfunction "2_2") (pintype "passive"))
      (node (ref "U3") (pin "23") (pinfunction "XERR_23") (pintype "output"))
    )
    (net (code "102") (name "Net-(U4-IREF)") (class "Default")
      (node (ref "R7") (pin "2") (pinfunction "2_2") (pintype "passive"))
      (node (ref "U4") (pin "27") (pinfunction "IREF_27") (pintype "input"))
    )
    (net (code "103") (name "Net-(U4-XERR)") (class "Default")
      (node (ref "R8") (pin "2") (pinfunction "2_2") (pintype "passive"))
      (node (ref "U4") (pin "23") (pinfunction "XERR_23") (pintype "output"))
    )
    (net (code "104") (name "Net-(U6-AREF)") (class "Default")
      (node (ref "C2") (pin "2") (pinfunction "2_2") (pintype "passive"))
      (node (ref "U6") (pin "20") (pinfunction "AREF_20") (pintype "input"))
    )
    (net (code "105") (name "Net-(U6-PB6)") (class "Default")
      (node (ref "C17") (pin "2") (pinfunction "2_2") (pintype "passive"))
      (node (ref "Q2") (pin "1") (pinfunction "1_1") (pintype "passive"))
      (node (ref "U6") (pin "7") (pinfunction "PB6_7") (pintype "bidirectional"))
    )
    (net (code "106") (name "Net-(U6-PB7)") (class "Default")
      (node (ref "C16") (pin "1") (pinfunction "1_1") (pintype "passive"))
      (node (ref "Q2") (pin "2") (pinfunction "2_2") (pintype "passive"))
      (node (ref "U6") (pin "8") (pinfunction "PB7_8") (pintype "bidirectional"))
    )
    (net (code "107") (name "Net-(WS1-PadDOUT)") (class "Default")
      (node (ref "WS1") (pin "DOUT") (pinfunction "DOUT_DOUT") (pintype "bidirectional"))
      (node (ref "WS2") (pin "DIN") (pinfunction "DIN_DIN") (pintype "bidirectional"))
    )
    (net (code "108") (name "Net-(WS2-PadDOUT)") (class "Default")
      (node (ref "WS2") (pin "DOUT") (pinfunction "DOUT_DOUT") (pintype "bidirectional"))
      (node (ref "WS3") (pin "DIN") (pinfunction "DIN_DIN") (pintype "bidirectional"))
    )
    (net (code "109") (name "Net-(WS3-PadDOUT)") (class "Default")
      (node (ref "WS3") (pin "DOUT") (pinfunction "DOUT_DOUT") (pintype "bidirectional"))
      (node (ref "WS4") (pin "DIN") (pinfunction "DIN_DIN") (pintype "bidirectional"))
    )
    (net (code "110") (name "Net-(WS4-PadDOUT)") (class "Default")
      (node (ref "WS4") (pin "DOUT") (pinfunction "DOUT_DOUT") (pintype "bidirectional"))
      (node (ref "WS5") (pin "DIN") (pinfunction "DIN_DIN") (pintype "bidirectional"))
    )
    (net (code "111") (name "Net-(WS5-PadDOUT)") (class "Default")
      (node (ref "WS5") (pin "DOUT") (pinfunction "DOUT_DOUT") (pintype "bidirectional"))
      (node (ref "WS6") (pin "DIN") (pinfunction "DIN_DIN") (pintype "bidirectional"))
    )
    (net (code "112") (name "Net-(WS6-PadDOUT)") (class "Default")
      (node (ref "WS6") (pin "DOUT") (pinfunction "DOUT_DOUT") (pintype "bidirectional"))
      (node (ref "WS7") (pin "DIN") (pinfunction "DIN_DIN") (pintype "bidirectional"))
    )
    (net (code "113") (name "Net-(WS7-PadDOUT)") (class "Default")
      (node (ref "WS7") (pin "DOUT") (pinfunction "DOUT_DOUT") (pintype "bidirectional"))
      (node (ref "WS8") (pin "DIN") (pinfunction "DIN_DIN") (pintype "bidirectional"))
    )
    (net (code "114") (name "Net-(WS8-PadDOUT)") (class "Default")
      (node (ref "WS8") (pin "DOUT") (pinfunction "DOUT_DOUT") (pintype "bidirectional"))
      (node (ref "WS9") (pin "DIN") (pinfunction "DIN_DIN") (pintype "bidirectional"))
    )
    (net (code "115") (name "Net-(WS10-PadDIN)") (class "Default")
      (node (ref "WS10") (pin "DIN") (pinfunction "DIN_DIN") (pintype "bidirectional"))
      (node (ref "WS9") (pin "DOUT") (pinfunction "DOUT_DOUT") (pintype "bidirectional"))
    )
    (net (code "116") (name "VCC") (class "Default")
      (node (ref "C1") (pin "2") (pinfunction "2_2") (pintype "passive"))
      (node (ref "C10") (pin "+") (pinfunction "+_+") (pintype "passive"))
      (node (ref "C11") (pin "+") (pinfunction "+_+") (pintype "passive"))
      (node (ref "C12") (pin "+") (pinfunction "+_+") (pintype "passive"))
      (node (ref "C13") (pin "1") (pinfunction "1_1") (pintype "passive"))
      (node (ref "C14") (pin "1") (pinfunction "1_1") (pintype "passive"))
      (node (ref "C15") (pin "1") (pinfunction "1_1") (pintype "passive"))
      (node (ref "C18") (pin "+") (pinfunction "+_+") (pintype "passive"))
      (node (ref "C19") (pin "1") (pinfunction "1_1") (pintype "passive"))
      (node (ref "C20") (pin "1") (pinfunction "1_1") (pintype "passive"))
      (node (ref "C21") (pin "1") (pinfunction "1_1") (pintype "passive"))
      (node (ref "C22") (pin "1") (pinfunction "1_1") (pintype "passive"))
      (node (ref "C23") (pin "1") (pinfunction "1_1") (pintype "passive"))
      (node (ref "C24") (pin "1") (pinfunction "1_1") (pintype "passive"))
      (node (ref "C25") (pin "1") (pinfunction "1_1") (pintype "passive"))
      (node (ref "C26") (pin "1") (pinfunction "1_1") (pintype "passive"))
      (node (ref "C27") (pin "1") (pinfunction "1_1") (pintype "passive"))
      (node (ref "C3") (pin "1") (pinfunction "1_1") (pintype "passive"))
      (node (ref "C4") (pin "1") (pinfunction "1_1") (pintype "passive"))
      (node (ref "C5") (pin "1") (pinfunction "1_1") (pintype "passive"))
      (node (ref "C6") (pin "1") (pinfunction "1_1") (pintype "passive"))
      (node (ref "C7") (pin "1") (pinfunction "1_1") (pintype "passive"))
      (node (ref "C8") (pin "1") (pinfunction "1_1") (pintype "passive"))
      (node (ref "C9") (pin "+") (pinfunction "+_+") (pintype "passive"))
      (node (ref "D1") (pin "2") (pinfunction "+_2") (pintype "passive"))
      (node (ref "D10") (pin "2") (pinfunction "+_2") (pintype "passive"))
      (node (ref "D11") (pin "2") (pinfunction "+_2") (pintype "passive"))
      (node (ref "D12") (pin "2") (pinfunction "+_2") (pintype "passive"))
      (node (ref "D13") (pin "2") (pinfunction "+_2") (pintype "passive"))
      (node (ref "D14") (pin "2") (pinfunction "+_2") (pintype "passive"))
      (node (ref "D15") (pin "2") (pinfunction "+_2") (pintype "passive"))
      (node (ref "D16") (pin "2") (pinfunction "+_2") (pintype "passive"))
      (node (ref "D17") (pin "2") (pinfunction "+_2") (pintype "passive"))
      (node (ref "D18") (pin "2") (pinfunction "+_2") (pintype "passive"))
      (node (ref "D19") (pin "2") (pinfunction "+_2") (pintype "passive"))
      (node (ref "D2") (pin "2") (pinfunction "+_2") (pintype "passive"))
      (node (ref "D20") (pin "2") (pinfunction "+_2") (pintype "passive"))
      (node (ref "D21") (pin "2") (pinfunction "+_2") (pintype "passive"))
      (node (ref "D22") (pin "2") (pinfunction "+_2") (pintype "passive"))
      (node (ref "D23") (pin "2") (pinfunction "+_2") (pintype "passive"))
      (node (ref "D24") (pin "2") (pinfunction "+_2") (pintype "passive"))
      (node (ref "D25") (pin "2") (pinfunction "+_2") (pintype "passive"))
      (node (ref "D26") (pin "2") (pinfunction "+_2") (pintype "passive"))
      (node (ref "D27") (pin "2") (pinfunction "+_2") (pintype "passive"))
      (node (ref "D28") (pin "2") (pinfunction "+_2") (pintype "passive"))
      (node (ref "D29") (pin "2") (pinfunction "+_2") (pintype "passive"))
      (node (ref "D3") (pin "2") (pinfunction "+_2") (pintype "passive"))
      (node (ref "D30") (pin "2") (pinfunction "+_2") (pintype "passive"))
      (node (ref "D31") (pin "2") (pinfunction "+_2") (pintype "passive"))
      (node (ref "D32") (pin "2") (pinfunction "+_2") (pintype "passive"))
      (node (ref "D33") (pin "2") (pinfunction "+_2") (pintype "passive"))
      (node (ref "D34") (pin "2") (pinfunction "+_2") (pintype "passive"))
      (node (ref "D35") (pin "2") (pinfunction "+_2") (pintype "passive"))
      (node (ref "D36") (pin "2") (pinfunction "+_2") (pintype "passive"))
      (node (ref "D37") (pin "2") (pinfunction "+_2") (pintype "passive"))
      (node (ref "D38") (pin "2") (pinfunction "+_2") (pintype "passive"))
      (node (ref "D39") (pin "2") (pinfunction "+_2") (pintype "passive"))
      (node (ref "D4") (pin "2") (pinfunction "+_2") (pintype "passive"))
      (node (ref "D40") (pin "2") (pinfunction "+_2") (pintype "passive"))
      (node (ref "D41") (pin "2") (pinfunction "+_2") (pintype "passive"))
      (node (ref "D42") (pin "2") (pinfunction "+_2") (pintype "passive"))
      (node (ref "D43") (pin "2") (pinfunction "+_2") (pintype "passive"))
      (node (ref "D44") (pin "2") (pinfunction "+_2") (pintype "passive"))
      (node (ref "D45") (pin "2") (pinfunction "+_2") (pintype "passive"))
      (node (ref "D46") (pin "2") (pinfunction "+_2") (pintype "passive"))
      (node (ref "D47") (pin "2") (pinfunction "+_2") (pintype "passive"))
      (node (ref "D48") (pin "2") (pinfunction "+_2") (pintype "passive"))
      (node (ref "D49") (pin "2") (pinfunction "+_2") (pintype "passive"))
      (node (ref "D5") (pin "2") (pinfunction "+_2") (pintype "passive"))
      (node (ref "D50") (pin "2") (pinfunction "+_2") (pintype "passive"))
      (node (ref "D51") (pin "2") (pinfunction "+_2") (pintype "passive"))
      (node (ref "D52") (pin "2") (pinfunction "+_2") (pintype "passive"))
      (node (ref "D53") (pin "2") (pinfunction "+_2") (pintype "passive"))
      (node (ref "D54") (pin "2") (pinfunction "+_2") (pintype "passive"))
      (node (ref "D55") (pin "2") (pinfunction "+_2") (pintype "passive"))
      (node (ref "D56") (pin "2") (pinfunction "+_2") (pintype "passive"))
      (node (ref "D57") (pin "2") (pinfunction "+_2") (pintype "passive"))
      (node (ref "D58") (pin "2") (pinfunction "+_2") (pintype "passive"))
      (node (ref "D59") (pin "2") (pinfunction "+_2") (pintype "passive"))
      (node (ref "D6") (pin "2") (pinfunction "+_2") (pintype "passive"))
      (node (ref "D60") (pin "2") (pinfunction "+_2") (pintype "passive"))
      (node (ref "D61") (pin "2") (pinfunction "+_2") (pintype "passive"))
      (node (ref "D62") (pin "2") (pinfunction "+_2") (pintype "passive"))
      (node (ref "D63") (pin "2") (pinfunction "+_2") (pintype "passive"))
      (node (ref "D64") (pin "2") (pinfunction "+_2") (pintype "passive"))
      (node (ref "D7") (pin "2") (pinfunction "+_2") (pintype "passive"))
      (node (ref "D8") (pin "2") (pinfunction "+_2") (pintype "passive"))
      (node (ref "D9") (pin "2") (pinfunction "+_2") (pintype "passive"))
      (node (ref "R11") (pin "1") (pinfunction "1_1") (pintype "passive"))
      (node (ref "R12") (pin "1") (pinfunction "1_1") (pintype "passive"))
      (node (ref "R13") (pin "1") (pinfunction "1_1") (pintype "passive"))
      (node (ref "R14") (pin "1") (pinfunction "1_1") (pintype "passive"))
      (node (ref "R15") (pin "1") (pinfunction "1_1") (pintype "passive"))
      (node (ref "R16") (pin "1") (pinfunction "1_1") (pintype "passive"))
      (node (ref "R17") (pin "1") (pinfunction "1_1") (pintype "passive"))
      (node (ref "R2") (pin "1") (pinfunction "1_1") (pintype "passive"))
      (node (ref "R4") (pin "1") (pinfunction "1_1") (pintype "passive"))
      (node (ref "R6") (pin "1") (pinfunction "1_1") (pintype "passive"))
      (node (ref "R8") (pin "1") (pinfunction "1_1") (pintype "passive"))
      (node (ref "U$2") (pin "1") (pinfunction "P$1_1") (pintype "bidirectional"))
      (node (ref "U$2") (pin "10") (pinfunction "P$10_10") (pintype "bidirectional"))
      (node (ref "U$2") (pin "7") (pinfunction "P$7_7") (pintype "bidirectional"))
      (node (ref "U$2") (pin "9") (pinfunction "P$9_9") (pintype "bidirectional"))
      (node (ref "U$3") (pin "2") (pinfunction "P$2_2") (pintype "bidirectional"))
      (node (ref "U1") (pin "28") (pinfunction "VCC_28") (pintype "power_in"))
      (node (ref "U2") (pin "28") (pinfunction "VCC_28") (pintype "power_in"))
      (node (ref "U3") (pin "28") (pinfunction "VCC_28") (pintype "power_in"))
      (node (ref "U4") (pin "28") (pinfunction "VCC_28") (pintype "power_in"))
      (node (ref "U6") (pin "18") (pinfunction "AVCC_18") (pintype "power_in"))
      (node (ref "U6") (pin "4") (pinfunction "VCC_2_4") (pintype "power_in"))
      (node (ref "U6") (pin "6") (pinfunction "VCC_6") (pintype "power_in"))
      (node (ref "WS1") (pin "VDD") (pinfunction "VDD_VDD") (pintype "bidirectional"))
      (node (ref "WS10") (pin "VDD") (pinfunction "VDD_VDD") (pintype "bidirectional"))
      (node (ref "WS2") (pin "VDD") (pinfunction "VDD_VDD") (pintype "bidirectional"))
      (node (ref "WS3") (pin "VDD") (pinfunction "VDD_VDD") (pintype "bidirectional"))
      (node (ref "WS4") (pin "VDD") (pinfunction "VDD_VDD") (pintype "bidirectional"))
      (node (ref "WS5") (pin "VDD") (pinfunction "VDD_VDD") (pintype "bidirectional"))
      (node (ref "WS6") (pin "VDD") (pinfunction "VDD_VDD") (pintype "bidirectional"))
      (node (ref "WS7") (pin "VDD") (pinfunction "VDD_VDD") (pintype "bidirectional"))
      (node (ref "WS8") (pin "VDD") (pinfunction "VDD_VDD") (pintype "bidirectional"))
      (node (ref "WS9") (pin "VDD") (pinfunction "VDD_VDD") (pintype "bidirectional"))
    )
    (net (code "117") (name "unconnected-(U1-TEST-Pad26)") (class "Default")
      (node (ref "U1") (pin "26") (pinfunction "TEST_26") (pintype "input"))
    )
    (net (code "118") (name "unconnected-(U2-TEST-Pad26)") (class "Default")
      (node (ref "U2") (pin "26") (pinfunction "TEST_26") (pintype "input"))
    )
    (net (code "119") (name "unconnected-(U3-TEST-Pad26)") (class "Default")
      (node (ref "U3") (pin "26") (pinfunction "TEST_26") (pintype "input"))
    )
    (net (code "120") (name "unconnected-(U4-TEST-Pad26)") (class "Default")
      (node (ref "U4") (pin "26") (pinfunction "TEST_26") (pintype "input"))
    )
    (net (code "121") (name "unconnected-(WS10-PadDOUT)") (class "Default")
      (node (ref "WS10") (pin "DOUT") (pinfunction "DOUT_DOUT") (pintype "bidirectional"))
    )
  )
)
